# IO_iJoey.net
KiCad netlist of a schematic drawn in EAGLE
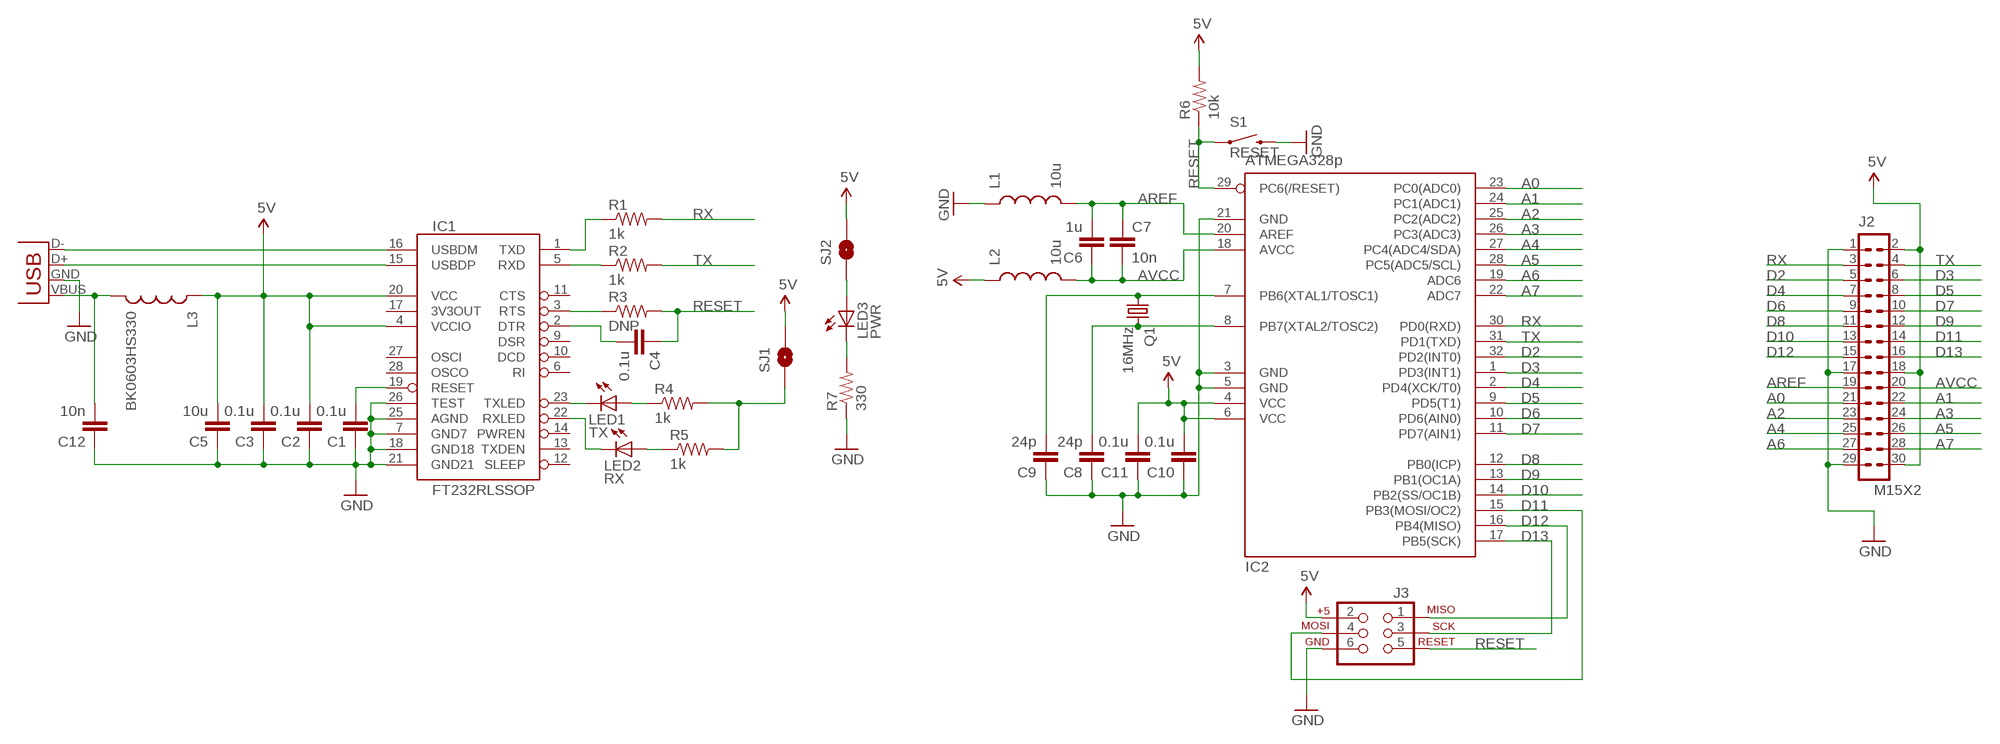
[diagram p0: schematic, sheet 1]

(export (version "E")
  (design (tool "Eeschema 10.0.6"))
  (components
    (comp (ref "C1")
      (value "0.1u")
      (footprint "eagle-import:0603-CAP")
      (libsource (lib "eagle-import") (part "CAP0603-CAP"))
    )
    (comp (ref "C2")
      (value "0.1u")
      (footprint "eagle-import:0603-CAP")
      (libsource (lib "eagle-import") (part "CAP0603-CAP"))
    )
    (comp (ref "C3")
      (value "0.1u")
      (footprint "eagle-import:0603-CAP")
      (libsource (lib "eagle-import") (part "CAP0603-CAP"))
    )
    (comp (ref "C4")
      (value "0.1u")
      (footprint "eagle-import:0603-CAP")
      (libsource (lib "eagle-import") (part "CAP0603-CAP"))
    )
    (comp (ref "C5")
      (value "10u")
      (footprint "eagle-import:0805")
      (libsource (lib "eagle-import") (part "CAP0805"))
    )
    (comp (ref "C6")
      (value "1u")
      (footprint "eagle-import:0603-CAP")
      (libsource (lib "eagle-import") (part "CAP0603-CAP"))
    )
    (comp (ref "C7")
      (value "10n")
      (footprint "eagle-import:0603-CAP")
      (libsource (lib "eagle-import") (part "CAP0603-CAP"))
    )
    (comp (ref "C8")
      (value "24p")
      (footprint "eagle-import:0603-CAP")
      (libsource (lib "eagle-import") (part "CAP0603-CAP"))
    )
    (comp (ref "C9")
      (value "24p")
      (footprint "eagle-import:0603-CAP")
      (libsource (lib "eagle-import") (part "CAP0603-CAP"))
    )
    (comp (ref "C10")
      (value "0.1u")
      (footprint "eagle-import:0603-CAP")
      (libsource (lib "eagle-import") (part "CAP0603-CAP"))
    )
    (comp (ref "C11")
      (value "0.1u")
      (footprint "eagle-import:0603-CAP")
      (libsource (lib "eagle-import") (part "CAP0603-CAP"))
    )
    (comp (ref "C12")
      (value "10n")
      (footprint "eagle-import:0603-CAP")
      (libsource (lib "eagle-import") (part "CAP0603-CAP"))
    )
    (comp (ref "IC1")
      (value "FT232RLSSOP")
      (footprint "eagle-import:SSOP28DB")
      (libsource (lib "eagle-import") (part "FT232RLSSOP"))
    )
    (comp (ref "IC2")
      (value "ATMEGA328p")
      (footprint "eagle-import:TQFP32-08")
      (fields (field (name "MPN") "ATMEGA8-16AU"))
      (libsource (lib "eagle-import") (part "MEGA8-AI"))
    )
    (comp (ref "J1")
      (value "USB-A-H")
      (footprint "eagle-import:USB-A-H")
      (libsource (lib "eagle-import") (part "USB-A-H"))
    )
    (comp (ref "J2")
      (value "M15X2")
      (footprint "eagle-import:2X15")
      (libsource (lib "eagle-import") (part "M15X2"))
    )
    (comp (ref "J3")
      (value "AVR_SPI_PRG_6PTH")
      (footprint "eagle-import:2X3")
      (libsource (lib "eagle-import") (part "AVR_SPI_PRG_6PTH"))
    )
    (comp (ref "L1")
      (value "10u")
      (footprint "eagle-import:0603")
      (libsource (lib "eagle-import") (part "INDUCTOR0603"))
    )
    (comp (ref "L2")
      (value "10u")
      (footprint "eagle-import:0603")
      (libsource (lib "eagle-import") (part "INDUCTOR0603"))
    )
    (comp (ref "L3")
      (value "BK0603HS330")
      (footprint "eagle-import:0603")
      (libsource (lib "eagle-import") (part "INDUCTOR0603"))
    )
    (comp (ref "LED1")
      (value "TX")
      (footprint "eagle-import:LED-0603")
      (libsource (lib "eagle-import") (part "LED0603"))
    )
    (comp (ref "LED2")
      (value "RX")
      (footprint "eagle-import:LED-0603")
      (libsource (lib "eagle-import") (part "LED0603"))
    )
    (comp (ref "LED3")
      (value "PWR")
      (footprint "eagle-import:LED-0603")
      (libsource (lib "eagle-import") (part "LED0603"))
    )
    (comp (ref "Q1")
      (value "16MHz")
      (footprint "eagle-import:HC49_GP")
      (libsource (lib "eagle-import") (part "CRYSTAL-GP"))
    )
    (comp (ref "R1")
      (value "1k")
      (footprint "eagle-import:0603-RES")
      (libsource (lib "eagle-import") (part "RESISTOR0603-RES"))
    )
    (comp (ref "R2")
      (value "1k")
      (footprint "eagle-import:0603-RES")
      (libsource (lib "eagle-import") (part "RESISTOR0603-RES"))
    )
    (comp (ref "R3")
      (value "DNP")
      (footprint "eagle-import:0603-RES")
      (libsource (lib "eagle-import") (part "RESISTOR0603-RES"))
    )
    (comp (ref "R4")
      (value "1k")
      (footprint "eagle-import:0603-RES")
      (libsource (lib "eagle-import") (part "RESISTOR0603-RES"))
    )
    (comp (ref "R5")
      (value "1k")
      (footprint "eagle-import:0603-RES")
      (libsource (lib "eagle-import") (part "RESISTOR0603-RES"))
    )
    (comp (ref "R6")
      (value "10k")
      (footprint "eagle-import:0603-RES")
      (libsource (lib "eagle-import") (part "RESISTOR0603-RES"))
    )
    (comp (ref "R7")
      (value "330")
      (footprint "eagle-import:0603-RES")
      (libsource (lib "eagle-import") (part "RESISTOR0603-RES"))
    )
    (comp (ref "S1")
      (value "RESET")
      (footprint "eagle-import:TACTILE-SWITCH-1101NE")
      (libsource (lib "eagle-import") (part "SWITCH-MOMENTARY-2-SMD-1101NE"))
    )
    (comp (ref "SJ1")
      (value "SOLDERJUMPERNC")
      (footprint "eagle-import:SJ_2S")
      (libsource (lib "eagle-import") (part "SOLDERJUMPERNC"))
    )
    (comp (ref "SJ2")
      (value "SOLDERJUMPERNC")
      (footprint "eagle-import:SJ_2S")
      (libsource (lib "eagle-import") (part "SOLDERJUMPERNC"))
    )
  )
  (nets
    (net (code "1") (name "/A0") (class "Default")
      (node (ref "IC2") (pin "23") (pinfunction "PC0(ADC0)_23") (pintype "bidirectional"))
      (node (ref "J2") (pin "21") (pinfunction "21_21") (pintype "bidirectional"))
    )
    (net (code "2") (name "/A1") (class "Default")
      (node (ref "IC2") (pin "24") (pinfunction "PC1(ADC1)_24") (pintype "bidirectional"))
      (node (ref "J2") (pin "22") (pinfunction "22_22") (pintype "bidirectional"))
    )
    (net (code "3") (name "/A2") (class "Default")
      (node (ref "IC2") (pin "25") (pinfunction "PC2(ADC2)_25") (pintype "bidirectional"))
      (node (ref "J2") (pin "23") (pinfunction "23_23") (pintype "bidirectional"))
    )
    (net (code "4") (name "/A3") (class "Default")
      (node (ref "IC2") (pin "26") (pinfunction "PC3(ADC3)_26") (pintype "bidirectional"))
      (node (ref "J2") (pin "24") (pinfunction "24_24") (pintype "bidirectional"))
    )
    (net (code "5") (name "/A4") (class "Default")
      (node (ref "IC2") (pin "27") (pinfunction "PC4(ADC4/SDA)_27") (pintype "bidirectional"))
      (node (ref "J2") (pin "25") (pinfunction "25_25") (pintype "bidirectional"))
    )
    (net (code "6") (name "/A5") (class "Default")
      (node (ref "IC2") (pin "28") (pinfunction "PC5(ADC5/SCL)_28") (pintype "bidirectional"))
      (node (ref "J2") (pin "26") (pinfunction "26_26") (pintype "bidirectional"))
    )
    (net (code "7") (name "/A6") (class "Default")
      (node (ref "IC2") (pin "19") (pinfunction "ADC6_19") (pintype "bidirectional"))
      (node (ref "J2") (pin "27") (pinfunction "27_27") (pintype "bidirectional"))
    )
    (net (code "8") (name "/A7") (class "Default")
      (node (ref "IC2") (pin "22") (pinfunction "ADC7_22") (pintype "bidirectional"))
      (node (ref "J2") (pin "28") (pinfunction "28_28") (pintype "bidirectional"))
    )
    (net (code "9") (name "/AREF") (class "Default")
      (node (ref "C6") (pin "2") (pinfunction "2_2") (pintype "passive"))
      (node (ref "C7") (pin "1") (pinfunction "1_1") (pintype "passive"))
      (node (ref "IC2") (pin "20") (pinfunction "AREF_20") (pintype "passive"))
      (node (ref "J2") (pin "19") (pinfunction "19_19") (pintype "bidirectional"))
      (node (ref "L1") (pin "2") (pinfunction "2_2") (pintype "passive"))
    )
    (net (code "10") (name "/AVCC") (class "Default")
      (node (ref "C6") (pin "1") (pinfunction "1_1") (pintype "passive"))
      (node (ref "C7") (pin "2") (pinfunction "2_2") (pintype "passive"))
      (node (ref "IC2") (pin "18") (pinfunction "AVCC_18") (pintype "power_in"))
      (node (ref "J2") (pin "20") (pinfunction "20_20") (pintype "bidirectional"))
      (node (ref "L2") (pin "2") (pinfunction "2_2") (pintype "passive"))
    )
    (net (code "11") (name "/D2") (class "Default")
      (node (ref "IC2") (pin "32") (pinfunction "PD2(INT0)_32") (pintype "bidirectional"))
      (node (ref "J2") (pin "5") (pinfunction "5_5") (pintype "bidirectional"))
    )
    (net (code "12") (name "/D3") (class "Default")
      (node (ref "IC2") (pin "1") (pinfunction "PD3(INT1)_1") (pintype "bidirectional"))
      (node (ref "J2") (pin "6") (pinfunction "6_6") (pintype "bidirectional"))
    )
    (net (code "13") (name "/D4") (class "Default")
      (node (ref "IC2") (pin "2") (pinfunction "PD4(XCK/T0)_2") (pintype "bidirectional"))
      (node (ref "J2") (pin "7") (pinfunction "7_7") (pintype "bidirectional"))
    )
    (net (code "14") (name "/D5") (class "Default")
      (node (ref "IC2") (pin "9") (pinfunction "PD5(T1)_9") (pintype "bidirectional"))
      (node (ref "J2") (pin "8") (pinfunction "8_8") (pintype "bidirectional"))
    )
    (net (code "15") (name "/D6") (class "Default")
      (node (ref "IC2") (pin "10") (pinfunction "PD6(AIN0)_10") (pintype "bidirectional"))
      (node (ref "J2") (pin "9") (pinfunction "9_9") (pintype "bidirectional"))
    )
    (net (code "16") (name "/D7") (class "Default")
      (node (ref "IC2") (pin "11") (pinfunction "PD7(AIN1)_11") (pintype "bidirectional"))
      (node (ref "J2") (pin "10") (pinfunction "10_10") (pintype "bidirectional"))
    )
    (net (code "17") (name "/D8") (class "Default")
      (node (ref "IC2") (pin "12") (pinfunction "PB0(ICP)_12") (pintype "bidirectional"))
      (node (ref "J2") (pin "11") (pinfunction "11_11") (pintype "bidirectional"))
    )
    (net (code "18") (name "/D9") (class "Default")
      (node (ref "IC2") (pin "13") (pinfunction "PB1(OC1A)_13") (pintype "bidirectional"))
      (node (ref "J2") (pin "12") (pinfunction "12_12") (pintype "bidirectional"))
    )
    (net (code "19") (name "/D10") (class "Default")
      (node (ref "IC2") (pin "14") (pinfunction "PB2(SS/OC1B)_14") (pintype "bidirectional"))
      (node (ref "J2") (pin "13") (pinfunction "13_13") (pintype "bidirectional"))
    )
    (net (code "20") (name "/D11") (class "Default")
      (node (ref "IC2") (pin "15") (pinfunction "PB3(MOSI/OC2)_15") (pintype "bidirectional"))
      (node (ref "J2") (pin "14") (pinfunction "14_14") (pintype "bidirectional"))
      (node (ref "J3") (pin "4") (pinfunction "4_4") (pintype "passive"))
    )
    (net (code "21") (name "/D12") (class "Default")
      (node (ref "IC2") (pin "16") (pinfunction "PB4(MISO)_16") (pintype "bidirectional"))
      (node (ref "J2") (pin "15") (pinfunction "15_15") (pintype "bidirectional"))
      (node (ref "J3") (pin "1") (pinfunction "1_1") (pintype "passive"))
    )
    (net (code "22") (name "/D13") (class "Default")
      (node (ref "IC2") (pin "17") (pinfunction "PB5(SCK)_17") (pintype "bidirectional"))
      (node (ref "J2") (pin "16") (pinfunction "16_16") (pintype "bidirectional"))
      (node (ref "J3") (pin "3") (pinfunction "3_3") (pintype "passive"))
    )
    (net (code "23") (name "/RESET") (class "Default")
      (node (ref "C4") (pin "1") (pinfunction "1_1") (pintype "passive"))
      (node (ref "IC2") (pin "29") (pinfunction "PC6(/RESET)_29") (pintype "bidirectional"))
      (node (ref "J3") (pin "5") (pinfunction "5_5") (pintype "passive"))
      (node (ref "R3") (pin "2") (pinfunction "2_2") (pintype "passive"))
      (node (ref "R6") (pin "1") (pinfunction "1_1") (pintype "passive"))
      (node (ref "S1") (pin "P$1") (pinfunction "1_P$1") (pintype "passive"))
    )
    (net (code "24") (name "/RX") (class "Default")
      (node (ref "IC2") (pin "30") (pinfunction "PD0(RXD)_30") (pintype "bidirectional"))
      (node (ref "J2") (pin "3") (pinfunction "3_3") (pintype "bidirectional"))
      (node (ref "R1") (pin "2") (pinfunction "2_2") (pintype "passive"))
    )
    (net (code "25") (name "/TX") (class "Default")
      (node (ref "IC2") (pin "31") (pinfunction "PD1(TXD)_31") (pintype "bidirectional"))
      (node (ref "J2") (pin "4") (pinfunction "4_4") (pintype "bidirectional"))
      (node (ref "R2") (pin "2") (pinfunction "2_2") (pintype "passive"))
    )
    (net (code "26") (name "5V") (class "Default")
      (node (ref "C10") (pin "2") (pinfunction "2_2") (pintype "passive"))
      (node (ref "C11") (pin "2") (pinfunction "2_2") (pintype "passive"))
      (node (ref "C2") (pin "2") (pinfunction "2_2") (pintype "passive"))
      (node (ref "C3") (pin "2") (pinfunction "2_2") (pintype "passive"))
      (node (ref "C5") (pin "2") (pinfunction "2_2") (pintype "passive"))
      (node (ref "IC1") (pin "20") (pinfunction "VCC_20") (pintype "power_in"))
      (node (ref "IC1") (pin "4") (pinfunction "VCCIO_4") (pintype "power_in"))
      (node (ref "IC2") (pin "4") (pinfunction "VCC_4") (pintype "power_in"))
      (node (ref "IC2") (pin "6") (pinfunction "VCC_6") (pintype "power_in"))
      (node (ref "J2") (pin "18") (pinfunction "18_18") (pintype "bidirectional"))
      (node (ref "J2") (pin "2") (pinfunction "2_2") (pintype "bidirectional"))
      (node (ref "J2") (pin "30") (pinfunction "30_30") (pintype "bidirectional"))
      (node (ref "J3") (pin "2") (pinfunction "2_2") (pintype "passive"))
      (node (ref "L2") (pin "1") (pinfunction "1_1") (pintype "passive"))
      (node (ref "L3") (pin "1") (pinfunction "1_1") (pintype "passive"))
      (node (ref "R6") (pin "2") (pinfunction "2_2") (pintype "passive"))
      (node (ref "SJ1") (pin "2") (pinfunction "2_2") (pintype "passive"))
      (node (ref "SJ2") (pin "2") (pinfunction "2_2") (pintype "passive"))
    )
    (net (code "27") (name "GND") (class "Default")
      (node (ref "C1") (pin "1") (pinfunction "1_1") (pintype "passive"))
      (node (ref "C10") (pin "1") (pinfunction "1_1") (pintype "passive"))
      (node (ref "C11") (pin "1") (pinfunction "1_1") (pintype "passive"))
      (node (ref "C12") (pin "1") (pinfunction "1_1") (pintype "passive"))
      (node (ref "C2") (pin "1") (pinfunction "1_1") (pintype "passive"))
      (node (ref "C3") (pin "1") (pinfunction "1_1") (pintype "passive"))
      (node (ref "C5") (pin "1") (pinfunction "1_1") (pintype "passive"))
      (node (ref "C8") (pin "1") (pinfunction "1_1") (pintype "passive"))
      (node (ref "C9") (pin "1") (pinfunction "1_1") (pintype "passive"))
      (node (ref "IC1") (pin "18") (pinfunction "GND18_18") (pintype "power_in"))
      (node (ref "IC1") (pin "21") (pinfunction "GND21_21") (pintype "power_in"))
      (node (ref "IC1") (pin "25") (pinfunction "AGND_25") (pintype "power_in"))
      (node (ref "IC1") (pin "26") (pinfunction "TEST_26") (pintype "input"))
      (node (ref "IC1") (pin "7") (pinfunction "GND7_7") (pintype "power_in"))
      (node (ref "IC2") (pin "21") (pinfunction "GND_21") (pintype "power_in"))
      (node (ref "IC2") (pin "3") (pinfunction "GND_3") (pintype "power_in"))
      (node (ref "IC2") (pin "5") (pinfunction "GND_5") (pintype "power_in"))
      (node (ref "J1") (pin "GND") (pinfunction "VBUS_GND") (pintype "bidirectional"))
      (node (ref "J2") (pin "1") (pinfunction "1_1") (pintype "bidirectional"))
      (node (ref "J2") (pin "17") (pinfunction "17_17") (pintype "bidirectional"))
      (node (ref "J2") (pin "29") (pinfunction "29_29") (pintype "bidirectional"))
      (node (ref "J3") (pin "6") (pinfunction "6_6") (pintype "passive"))
      (node (ref "L1") (pin "1") (pinfunction "1_1") (pintype "passive"))
      (node (ref "R7") (pin "1") (pinfunction "1_1") (pintype "passive"))
      (node (ref "S1") (pin "P$2") (pinfunction "2_P$2") (pintype "passive"))
    )
    (net (code "28") (name "Net-(IC1-DTR)") (class "Default")
      (node (ref "C4") (pin "2") (pinfunction "2_2") (pintype "passive"))
      (node (ref "IC1") (pin "2") (pinfunction "DTR_2") (pintype "output"))
    )
    (net (code "29") (name "Net-(IC1-RESET)") (class "Default")
      (node (ref "C1") (pin "2") (pinfunction "2_2") (pintype "passive"))
      (node (ref "IC1") (pin "19") (pinfunction "RESET_19") (pintype "input"))
    )
    (net (code "30") (name "Net-(IC1-RTS)") (class "Default")
      (node (ref "IC1") (pin "3") (pinfunction "RTS_3") (pintype "output"))
      (node (ref "R3") (pin "1") (pinfunction "1_1") (pintype "passive"))
    )
    (net (code "31") (name "Net-(IC1-RXD)") (class "Default")
      (node (ref "IC1") (pin "5") (pinfunction "RXD_5") (pintype "input"))
      (node (ref "R2") (pin "1") (pinfunction "1_1") (pintype "passive"))
    )
    (net (code "32") (name "Net-(IC1-RXLED)") (class "Default")
      (node (ref "IC1") (pin "22") (pinfunction "RXLED_22") (pintype "input"))
      (node (ref "LED2") (pin "C") (pinfunction "C_C") (pintype "passive"))
    )
    (net (code "33") (name "Net-(IC1-TXD)") (class "Default")
      (node (ref "IC1") (pin "1") (pinfunction "TXD_1") (pintype "output"))
      (node (ref "R1") (pin "1") (pinfunction "1_1") (pintype "passive"))
    )
    (net (code "34") (name "Net-(IC1-TXLED)") (class "Default")
      (node (ref "IC1") (pin "23") (pinfunction "TXLED_23") (pintype "input"))
      (node (ref "LED1") (pin "C") (pinfunction "C_C") (pintype "passive"))
    )
    (net (code "35") (name "Net-(IC1-USBDM)") (class "Default")
      (node (ref "IC1") (pin "16") (pinfunction "USBDM_16") (pintype "bidirectional"))
      (node (ref "J1") (pin "D-") (pinfunction "D+_D-") (pintype "bidirectional"))
    )
    (net (code "36") (name "Net-(IC1-USBDP)") (class "Default")
      (node (ref "IC1") (pin "15") (pinfunction "USBDP_15") (pintype "bidirectional"))
      (node (ref "J1") (pin "D+") (pinfunction "D-_D+") (pintype "bidirectional"))
    )
    (net (code "37") (name "Net-(IC2-PB6(XTAL1{slash}TOSC1))") (class "Default")
      (node (ref "C9") (pin "2") (pinfunction "2_2") (pintype "passive"))
      (node (ref "IC2") (pin "7") (pinfunction "PB6(XTAL1/TOSC1)_7") (pintype "bidirectional"))
      (node (ref "Q1") (pin "1") (pinfunction "1_1") (pintype "passive"))
    )
    (net (code "38") (name "Net-(IC2-PB7(XTAL2{slash}TOSC2))") (class "Default")
      (node (ref "C8") (pin "2") (pinfunction "2_2") (pintype "passive"))
      (node (ref "IC2") (pin "8") (pinfunction "PB7(XTAL2/TOSC2)_8") (pintype "bidirectional"))
      (node (ref "Q1") (pin "2") (pinfunction "2_2") (pintype "passive"))
    )
    (net (code "39") (name "Net-(J1-GND)") (class "Default")
      (node (ref "C12") (pin "2") (pinfunction "2_2") (pintype "passive"))
      (node (ref "J1") (pin "VBUS") (pinfunction "GND_VBUS") (pintype "bidirectional"))
      (node (ref "L3") (pin "2") (pinfunction "2_2") (pintype "passive"))
    )
    (net (code "40") (name "Net-(LED1-PadA)") (class "Default")
      (node (ref "LED1") (pin "A") (pinfunction "A_A") (pintype "passive"))
      (node (ref "R4") (pin "1") (pinfunction "1_1") (pintype "passive"))
    )
    (net (code "41") (name "Net-(LED2-PadA)") (class "Default")
      (node (ref "LED2") (pin "A") (pinfunction "A_A") (pintype "passive"))
      (node (ref "R5") (pin "1") (pinfunction "1_1") (pintype "passive"))
    )
    (net (code "42") (name "Net-(LED3-PadA)") (class "Default")
      (node (ref "LED3") (pin "A") (pinfunction "A_A") (pintype "passive"))
      (node (ref "SJ2") (pin "1") (pinfunction "1_1") (pintype "passive"))
    )
    (net (code "43") (name "Net-(LED3-PadC)") (class "Default")
      (node (ref "LED3") (pin "C") (pinfunction "C_C") (pintype "passive"))
      (node (ref "R7") (pin "2") (pinfunction "2_2") (pintype "passive"))
    )
    (net (code "44") (name "Net-(R4-Pad2)") (class "Default")
      (node (ref "R4") (pin "2") (pinfunction "2_2") (pintype "passive"))
      (node (ref "R5") (pin "2") (pinfunction "2_2") (pintype "passive"))
      (node (ref "SJ1") (pin "1") (pinfunction "1_1") (pintype "passive"))
    )
    (net (code "45") (name "unconnected-(IC1-3V3OUT-Pad17)") (class "Default")
      (node (ref "IC1") (pin "17") (pinfunction "3V3OUT_17") (pintype "output"))
    )
    (net (code "46") (name "unconnected-(IC1-CTS-Pad11)") (class "Default")
      (node (ref "IC1") (pin "11") (pinfunction "CTS_11") (pintype "input"))
    )
    (net (code "47") (name "unconnected-(IC1-DCD-Pad10)") (class "Default")
      (node (ref "IC1") (pin "10") (pinfunction "DCD_10") (pintype "input"))
    )
    (net (code "48") (name "unconnected-(IC1-DSR-Pad9)") (class "Default")
      (node (ref "IC1") (pin "9") (pinfunction "DSR_9") (pintype "input"))
    )
    (net (code "49") (name "unconnected-(IC1-OSCI-Pad27)") (class "Default")
      (node (ref "IC1") (pin "27") (pinfunction "OSCI_27") (pintype "input"))
    )
    (net (code "50") (name "unconnected-(IC1-OSCO-Pad28)") (class "Default")
      (node (ref "IC1") (pin "28") (pinfunction "OSCO_28") (pintype "output"))
    )
    (net (code "51") (name "unconnected-(IC1-PWREN-Pad14)") (class "Default")
      (node (ref "IC1") (pin "14") (pinfunction "PWREN_14") (pintype "input"))
    )
    (net (code "52") (name "unconnected-(IC1-RI-Pad6)") (class "Default")
      (node (ref "IC1") (pin "6") (pinfunction "RI_6") (pintype "input"))
    )
    (net (code "53") (name "unconnected-(IC1-SLEEP-Pad12)") (class "Default")
      (node (ref "IC1") (pin "12") (pinfunction "SLEEP_12") (pintype "input"))
    )
    (net (code "54") (name "unconnected-(IC1-TXDEN-Pad13)") (class "Default")
      (node (ref "IC1") (pin "13") (pinfunction "TXDEN_13") (pintype "input"))
    )
  )
)
